# step_dance_wiring.net
KiCad netlist of a schematic drawn in EAGLE
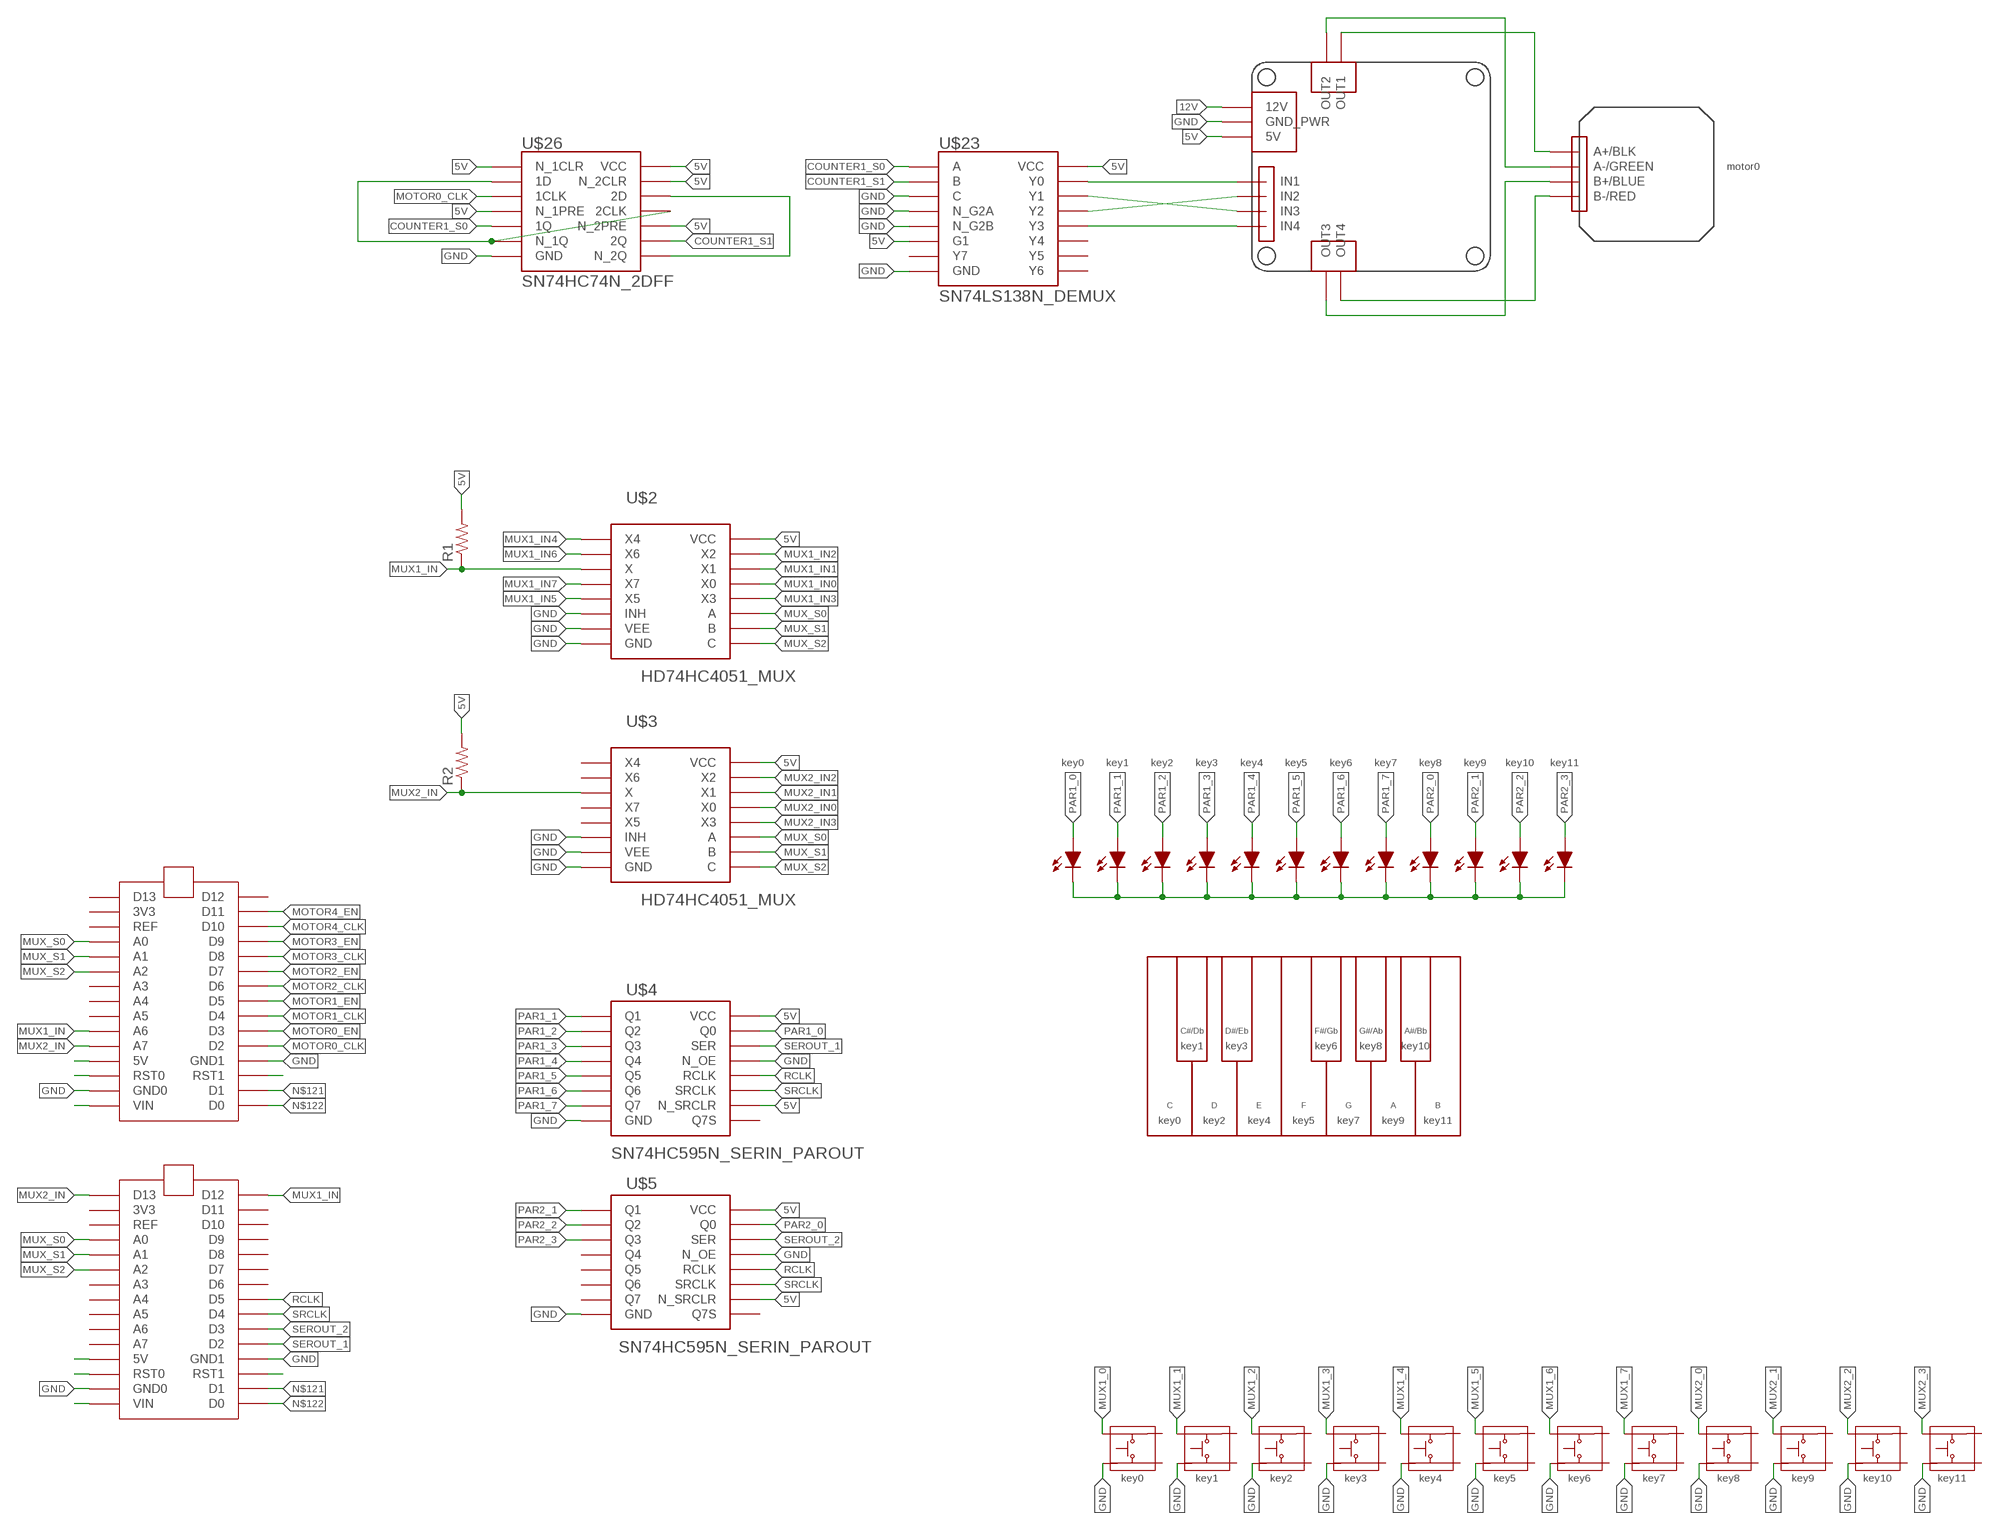
[diagram p0: schematic, sheet 1]

(export (version "E")
  (design (tool "Eeschema 10.0.6"))
  (components
    (comp (ref "LED1")
      (value "LED-5MM")
      (footprint "eagle-import:LED-5MM")
      (libsource (lib "eagle-import") (part "LED-5MM"))
    )
    (comp (ref "LED2")
      (value "LED-5MM")
      (footprint "eagle-import:LED-5MM")
      (libsource (lib "eagle-import") (part "LED-5MM"))
    )
    (comp (ref "LED3")
      (value "LED-5MM")
      (footprint "eagle-import:LED-5MM")
      (libsource (lib "eagle-import") (part "LED-5MM"))
    )
    (comp (ref "LED4")
      (value "LED-5MM")
      (footprint "eagle-import:LED-5MM")
      (libsource (lib "eagle-import") (part "LED-5MM"))
    )
    (comp (ref "LED5")
      (value "LED-5MM")
      (footprint "eagle-import:LED-5MM")
      (libsource (lib "eagle-import") (part "LED-5MM"))
    )
    (comp (ref "LED6")
      (value "LED-5MM")
      (footprint "eagle-import:LED-5MM")
      (libsource (lib "eagle-import") (part "LED-5MM"))
    )
    (comp (ref "LED7")
      (value "LED-5MM")
      (footprint "eagle-import:LED-5MM")
      (libsource (lib "eagle-import") (part "LED-5MM"))
    )
    (comp (ref "LED8")
      (value "LED-5MM")
      (footprint "eagle-import:LED-5MM")
      (libsource (lib "eagle-import") (part "LED-5MM"))
    )
    (comp (ref "LED9")
      (value "LED-5MM")
      (footprint "eagle-import:LED-5MM")
      (libsource (lib "eagle-import") (part "LED-5MM"))
    )
    (comp (ref "LED10")
      (value "LED-5MM")
      (footprint "eagle-import:LED-5MM")
      (libsource (lib "eagle-import") (part "LED-5MM"))
    )
    (comp (ref "LED11")
      (value "LED-5MM")
      (footprint "eagle-import:LED-5MM")
      (libsource (lib "eagle-import") (part "LED-5MM"))
    )
    (comp (ref "LED12")
      (value "LED-5MM")
      (footprint "eagle-import:LED-5MM")
      (libsource (lib "eagle-import") (part "LED-5MM"))
    )
    (comp (ref "R1")
      (value "RES_AXIAL1/2W-0.5")
      (footprint "eagle-import:1_2W-0.5")
      (libsource (lib "eagle-import") (part "RES_AXIAL1/2W-0.5"))
    )
    (comp (ref "R2")
      (value "RES_AXIAL1/2W-0.5")
      (footprint "eagle-import:1_2W-0.5")
      (libsource (lib "eagle-import") (part "RES_AXIAL1/2W-0.5"))
    )
    (comp (ref "U$1")
      (value "ARDUNIO_NANO")
      (footprint "eagle-import:PINS")
      (libsource (lib "eagle-import") (part "ARDUNIO_NANO"))
    )
    (comp (ref "U$2")
      (value "HD74HC4051_MUX")
      (footprint "eagle-import:PINS")
      (libsource (lib "eagle-import") (part "HD74HC4051_MUX"))
    )
    (comp (ref "U$3")
      (value "HD74HC4051_MUX")
      (footprint "eagle-import:PINS")
      (libsource (lib "eagle-import") (part "HD74HC4051_MUX"))
    )
    (comp (ref "U$4")
      (value "SN74HC595N_SERIN_PAROUT")
      (footprint "eagle-import:PINS")
      (libsource (lib "eagle-import") (part "SN74HC595N_SERIN_PAROUT"))
    )
    (comp (ref "U$5")
      (value "SN74HC595N_SERIN_PAROUT")
      (footprint "eagle-import:PINS")
      (libsource (lib "eagle-import") (part "SN74HC595N_SERIN_PAROUT"))
    )
    (comp (ref "U$7")
      (value "MOTOR_DRIVER_HILETGO")
      (footprint "eagle-import:PINS")
      (libsource (lib "eagle-import") (part "MOTOR_DRIVER_HILETGO"))
    )
    (comp (ref "U$8")
      (value "STEPPER")
      (footprint "eagle-import:PINS")
      (libsource (lib "eagle-import") (part "STEPPER"))
    )
    (comp (ref "U$9")
      (value "KEYBOARD")
      (footprint "eagle-import:PINS")
      (libsource (lib "eagle-import") (part "KEYBOARD"))
    )
    (comp (ref "U$10")
      (value "PUSHBUTTON")
      (footprint "eagle-import:PINS")
      (libsource (lib "eagle-import") (part "PUSHBUTTON"))
    )
    (comp (ref "U$11")
      (value "PUSHBUTTON")
      (footprint "eagle-import:PINS")
      (libsource (lib "eagle-import") (part "PUSHBUTTON"))
    )
    (comp (ref "U$12")
      (value "PUSHBUTTON")
      (footprint "eagle-import:PINS")
      (libsource (lib "eagle-import") (part "PUSHBUTTON"))
    )
    (comp (ref "U$13")
      (value "PUSHBUTTON")
      (footprint "eagle-import:PINS")
      (libsource (lib "eagle-import") (part "PUSHBUTTON"))
    )
    (comp (ref "U$14")
      (value "PUSHBUTTON")
      (footprint "eagle-import:PINS")
      (libsource (lib "eagle-import") (part "PUSHBUTTON"))
    )
    (comp (ref "U$15")
      (value "PUSHBUTTON")
      (footprint "eagle-import:PINS")
      (libsource (lib "eagle-import") (part "PUSHBUTTON"))
    )
    (comp (ref "U$16")
      (value "PUSHBUTTON")
      (footprint "eagle-import:PINS")
      (libsource (lib "eagle-import") (part "PUSHBUTTON"))
    )
    (comp (ref "U$17")
      (value "PUSHBUTTON")
      (footprint "eagle-import:PINS")
      (libsource (lib "eagle-import") (part "PUSHBUTTON"))
    )
    (comp (ref "U$18")
      (value "PUSHBUTTON")
      (footprint "eagle-import:PINS")
      (libsource (lib "eagle-import") (part "PUSHBUTTON"))
    )
    (comp (ref "U$19")
      (value "PUSHBUTTON")
      (footprint "eagle-import:PINS")
      (libsource (lib "eagle-import") (part "PUSHBUTTON"))
    )
    (comp (ref "U$20")
      (value "PUSHBUTTON")
      (footprint "eagle-import:PINS")
      (libsource (lib "eagle-import") (part "PUSHBUTTON"))
    )
    (comp (ref "U$21")
      (value "PUSHBUTTON")
      (footprint "eagle-import:PINS")
      (libsource (lib "eagle-import") (part "PUSHBUTTON"))
    )
    (comp (ref "U$22")
      (value "ARDUNIO_NANO")
      (footprint "eagle-import:PINS")
      (libsource (lib "eagle-import") (part "ARDUNIO_NANO"))
    )
    (comp (ref "U$23")
      (value "SN74LS138N_DEMUX")
      (footprint "eagle-import:PINS")
      (libsource (lib "eagle-import") (part "SN74LS138N_DEMUX"))
    )
    (comp (ref "U$26")
      (value "SN74HC74N_2DFF")
      (footprint "eagle-import:PINS")
      (libsource (lib "eagle-import") (part "SN74HC74N_2DFF"))
    )
  )
  (nets
    (net (code "1") (name "5V") (class "Default")
      (node (ref "R1") (pin "2") (pinfunction "2_2") (pintype "passive"))
      (node (ref "R2") (pin "2") (pinfunction "2_2") (pintype "passive"))
      (node (ref "U$2") (pin "P$6") (pinfunction "VCC_P$6") (pintype "output"))
      (node (ref "U$23") (pin "P$4") (pinfunction "G1_P$4") (pintype "output"))
      (node (ref "U$23") (pin "P$8") (pinfunction "VCC_P$8") (pintype "output"))
      (node (ref "U$26") (pin "P$11") (pinfunction "N_2CLR_P$11") (pintype "output"))
      (node (ref "U$26") (pin "P$12") (pinfunction "N_2PRE_P$12") (pintype "output"))
      (node (ref "U$26") (pin "P$14") (pinfunction "VCC_P$14") (pintype "output"))
      (node (ref "U$26") (pin "P$8") (pinfunction "N_1CLR_P$8") (pintype "output"))
      (node (ref "U$26") (pin "P$9") (pinfunction "N_1PRE_P$9") (pintype "output"))
      (node (ref "U$3") (pin "P$6") (pinfunction "VCC_P$6") (pintype "output"))
      (node (ref "U$4") (pin "P$16") (pinfunction "VCC_P$16") (pintype "output"))
      (node (ref "U$4") (pin "P$3") (pinfunction "N_SRCLR_P$3") (pintype "output"))
      (node (ref "U$5") (pin "P$16") (pinfunction "VCC_P$16") (pintype "output"))
      (node (ref "U$5") (pin "P$3") (pinfunction "N_SRCLR_P$3") (pintype "output"))
      (node (ref "U$7") (pin "P$1") (pinfunction "5V_P$1") (pintype "bidirectional"))
    )
    (net (code "2") (name "12V") (class "Default")
      (node (ref "U$7") (pin "P$2") (pinfunction "12V_P$2") (pintype "bidirectional"))
    )
    (net (code "3") (name "COUNTER1_S0") (class "Default")
      (node (ref "U$23") (pin "P$1") (pinfunction "A_P$1") (pintype "output"))
      (node (ref "U$26") (pin "P$3") (pinfunction "1Q_P$3") (pintype "output"))
    )
    (net (code "4") (name "COUNTER1_S1") (class "Default")
      (node (ref "U$23") (pin "P$2") (pinfunction "B_P$2") (pintype "output"))
      (node (ref "U$26") (pin "P$6") (pinfunction "2Q_P$6") (pintype "output"))
    )
    (net (code "5") (name "GND") (class "Default")
      (node (ref "U$1") (pin "P$25") (pinfunction "GND0_P$25") (pintype "bidirectional"))
      (node (ref "U$1") (pin "P$26") (pinfunction "GND1_P$26") (pintype "bidirectional"))
      (node (ref "U$10") (pin "P$2") (pinfunction "P$2_P$2") (pintype "bidirectional"))
      (node (ref "U$11") (pin "P$2") (pinfunction "P$2_P$2") (pintype "bidirectional"))
      (node (ref "U$12") (pin "P$2") (pinfunction "P$2_P$2") (pintype "bidirectional"))
      (node (ref "U$13") (pin "P$2") (pinfunction "P$2_P$2") (pintype "bidirectional"))
      (node (ref "U$14") (pin "P$2") (pinfunction "P$2_P$2") (pintype "bidirectional"))
      (node (ref "U$15") (pin "P$2") (pinfunction "P$2_P$2") (pintype "bidirectional"))
      (node (ref "U$16") (pin "P$2") (pinfunction "P$2_P$2") (pintype "bidirectional"))
      (node (ref "U$17") (pin "P$2") (pinfunction "P$2_P$2") (pintype "bidirectional"))
      (node (ref "U$18") (pin "P$2") (pinfunction "P$2_P$2") (pintype "bidirectional"))
      (node (ref "U$19") (pin "P$2") (pinfunction "P$2_P$2") (pintype "bidirectional"))
      (node (ref "U$2") (pin "P$4") (pinfunction "GND_P$4") (pintype "output"))
      (node (ref "U$2") (pin "P$5") (pinfunction "INH_P$5") (pintype "output"))
      (node (ref "U$2") (pin "P$7") (pinfunction "VEE_P$7") (pintype "output"))
      (node (ref "U$20") (pin "P$2") (pinfunction "P$2_P$2") (pintype "bidirectional"))
      (node (ref "U$21") (pin "P$2") (pinfunction "P$2_P$2") (pintype "bidirectional"))
      (node (ref "U$22") (pin "P$25") (pinfunction "GND0_P$25") (pintype "bidirectional"))
      (node (ref "U$22") (pin "P$26") (pinfunction "GND1_P$26") (pintype "bidirectional"))
      (node (ref "U$23") (pin "P$3") (pinfunction "C_P$3") (pintype "output"))
      (node (ref "U$23") (pin "P$5") (pinfunction "GND_P$5") (pintype "output"))
      (node (ref "U$23") (pin "P$6") (pinfunction "N_G2A_P$6") (pintype "output"))
      (node (ref "U$23") (pin "P$7") (pinfunction "N_G2B_P$7") (pintype "output"))
      (node (ref "U$26") (pin "P$7") (pinfunction "GND_P$7") (pintype "output"))
      (node (ref "U$3") (pin "P$4") (pinfunction "GND_P$4") (pintype "output"))
      (node (ref "U$3") (pin "P$5") (pinfunction "INH_P$5") (pintype "output"))
      (node (ref "U$3") (pin "P$7") (pinfunction "VEE_P$7") (pintype "output"))
      (node (ref "U$4") (pin "P$2") (pinfunction "GND_P$2") (pintype "output"))
      (node (ref "U$4") (pin "P$4") (pinfunction "N_OE_P$4") (pintype "output"))
      (node (ref "U$5") (pin "P$2") (pinfunction "GND_P$2") (pintype "output"))
      (node (ref "U$5") (pin "P$4") (pinfunction "N_OE_P$4") (pintype "output"))
      (node (ref "U$7") (pin "P$3") (pinfunction "GND_PWR_P$3") (pintype "bidirectional"))
    )
    (net (code "6") (name "MOTOR0_CLK") (class "Default")
      (node (ref "U$1") (pin "P$13") (pinfunction "D2_P$13") (pintype "bidirectional"))
      (node (ref "U$26") (pin "P$1") (pinfunction "1CLK_P$1") (pintype "output"))
    )
    (net (code "7") (name "MOTOR0_EN") (class "Default")
      (node (ref "U$1") (pin "P$14") (pinfunction "D3_P$14") (pintype "bidirectional"))
    )
    (net (code "8") (name "MOTOR1_CLK") (class "Default")
      (node (ref "U$1") (pin "P$15") (pinfunction "D4_P$15") (pintype "bidirectional"))
    )
    (net (code "9") (name "MOTOR1_EN") (class "Default")
      (node (ref "U$1") (pin "P$16") (pinfunction "D5_P$16") (pintype "bidirectional"))
    )
    (net (code "10") (name "MOTOR2_CLK") (class "Default")
      (node (ref "U$1") (pin "P$17") (pinfunction "D6_P$17") (pintype "bidirectional"))
    )
    (net (code "11") (name "MOTOR2_EN") (class "Default")
      (node (ref "U$1") (pin "P$18") (pinfunction "D7_P$18") (pintype "bidirectional"))
    )
    (net (code "12") (name "MOTOR3_CLK") (class "Default")
      (node (ref "U$1") (pin "P$19") (pinfunction "D8_P$19") (pintype "bidirectional"))
    )
    (net (code "13") (name "MOTOR3_EN") (class "Default")
      (node (ref "U$1") (pin "P$20") (pinfunction "D9_P$20") (pintype "bidirectional"))
    )
    (net (code "14") (name "MOTOR4_CLK") (class "Default")
      (node (ref "U$1") (pin "P$21") (pinfunction "D10_P$21") (pintype "bidirectional"))
    )
    (net (code "15") (name "MOTOR4_EN") (class "Default")
      (node (ref "U$1") (pin "P$22") (pinfunction "D11_P$22") (pintype "bidirectional"))
    )
    (net (code "16") (name "MUX1_0") (class "Default")
      (node (ref "U$10") (pin "P$1") (pinfunction "P$1_P$1") (pintype "bidirectional"))
    )
    (net (code "17") (name "MUX1_1") (class "Default")
      (node (ref "U$11") (pin "P$1") (pinfunction "P$1_P$1") (pintype "bidirectional"))
    )
    (net (code "18") (name "MUX1_2") (class "Default")
      (node (ref "U$12") (pin "P$1") (pinfunction "P$1_P$1") (pintype "bidirectional"))
    )
    (net (code "19") (name "MUX1_3") (class "Default")
      (node (ref "U$13") (pin "P$1") (pinfunction "P$1_P$1") (pintype "bidirectional"))
    )
    (net (code "20") (name "MUX1_4") (class "Default")
      (node (ref "U$14") (pin "P$1") (pinfunction "P$1_P$1") (pintype "bidirectional"))
    )
    (net (code "21") (name "MUX1_5") (class "Default")
      (node (ref "U$15") (pin "P$1") (pinfunction "P$1_P$1") (pintype "bidirectional"))
    )
    (net (code "22") (name "MUX1_6") (class "Default")
      (node (ref "U$19") (pin "P$1") (pinfunction "P$1_P$1") (pintype "bidirectional"))
    )
    (net (code "23") (name "MUX1_7") (class "Default")
      (node (ref "U$20") (pin "P$1") (pinfunction "P$1_P$1") (pintype "bidirectional"))
    )
    (net (code "24") (name "MUX1_IN") (class "Default")
      (node (ref "R1") (pin "1") (pinfunction "1_1") (pintype "passive"))
      (node (ref "U$1") (pin "P$9") (pinfunction "A6_P$9") (pintype "bidirectional"))
      (node (ref "U$2") (pin "P$8") (pinfunction "X_P$8") (pintype "output"))
      (node (ref "U$22") (pin "P$23") (pinfunction "D12_P$23") (pintype "bidirectional"))
    )
    (net (code "25") (name "MUX1_IN0") (class "Default")
      (node (ref "U$2") (pin "P$9") (pinfunction "X0_P$9") (pintype "output"))
    )
    (net (code "26") (name "MUX1_IN1") (class "Default")
      (node (ref "U$2") (pin "P$10") (pinfunction "X1_P$10") (pintype "output"))
    )
    (net (code "27") (name "MUX1_IN2") (class "Default")
      (node (ref "U$2") (pin "P$11") (pinfunction "X2_P$11") (pintype "output"))
    )
    (net (code "28") (name "MUX1_IN3") (class "Default")
      (node (ref "U$2") (pin "P$12") (pinfunction "X3_P$12") (pintype "output"))
    )
    (net (code "29") (name "MUX1_IN4") (class "Default")
      (node (ref "U$2") (pin "P$13") (pinfunction "X4_P$13") (pintype "output"))
    )
    (net (code "30") (name "MUX1_IN5") (class "Default")
      (node (ref "U$2") (pin "P$14") (pinfunction "X5_P$14") (pintype "output"))
    )
    (net (code "31") (name "MUX1_IN6") (class "Default")
      (node (ref "U$2") (pin "P$15") (pinfunction "X6_P$15") (pintype "output"))
    )
    (net (code "32") (name "MUX1_IN7") (class "Default")
      (node (ref "U$2") (pin "P$16") (pinfunction "X7_P$16") (pintype "output"))
    )
    (net (code "33") (name "MUX2_0") (class "Default")
      (node (ref "U$21") (pin "P$1") (pinfunction "P$1_P$1") (pintype "bidirectional"))
    )
    (net (code "34") (name "MUX2_1") (class "Default")
      (node (ref "U$16") (pin "P$1") (pinfunction "P$1_P$1") (pintype "bidirectional"))
    )
    (net (code "35") (name "MUX2_2") (class "Default")
      (node (ref "U$17") (pin "P$1") (pinfunction "P$1_P$1") (pintype "bidirectional"))
    )
    (net (code "36") (name "MUX2_3") (class "Default")
      (node (ref "U$18") (pin "P$1") (pinfunction "P$1_P$1") (pintype "bidirectional"))
    )
    (net (code "37") (name "MUX2_IN") (class "Default")
      (node (ref "R2") (pin "1") (pinfunction "1_1") (pintype "passive"))
      (node (ref "U$1") (pin "P$10") (pinfunction "A7_P$10") (pintype "bidirectional"))
      (node (ref "U$22") (pin "P$24") (pinfunction "D13_P$24") (pintype "bidirectional"))
      (node (ref "U$3") (pin "P$8") (pinfunction "X_P$8") (pintype "output"))
    )
    (net (code "38") (name "MUX2_IN0") (class "Default")
      (node (ref "U$3") (pin "P$9") (pinfunction "X0_P$9") (pintype "output"))
    )
    (net (code "39") (name "MUX2_IN1") (class "Default")
      (node (ref "U$3") (pin "P$10") (pinfunction "X1_P$10") (pintype "output"))
    )
    (net (code "40") (name "MUX2_IN2") (class "Default")
      (node (ref "U$3") (pin "P$11") (pinfunction "X2_P$11") (pintype "output"))
    )
    (net (code "41") (name "MUX2_IN3") (class "Default")
      (node (ref "U$3") (pin "P$12") (pinfunction "X3_P$12") (pintype "output"))
    )
    (net (code "42") (name "MUX_S0") (class "Default")
      (node (ref "U$1") (pin "P$3") (pinfunction "A0_P$3") (pintype "bidirectional"))
      (node (ref "U$2") (pin "P$1") (pinfunction "A_P$1") (pintype "output"))
      (node (ref "U$22") (pin "P$3") (pinfunction "A0_P$3") (pintype "bidirectional"))
      (node (ref "U$3") (pin "P$1") (pinfunction "A_P$1") (pintype "output"))
    )
    (net (code "43") (name "MUX_S1") (class "Default")
      (node (ref "U$1") (pin "P$4") (pinfunction "A1_P$4") (pintype "bidirectional"))
      (node (ref "U$2") (pin "P$2") (pinfunction "B_P$2") (pintype "output"))
      (node (ref "U$22") (pin "P$4") (pinfunction "A1_P$4") (pintype "bidirectional"))
      (node (ref "U$3") (pin "P$2") (pinfunction "B_P$2") (pintype "output"))
    )
    (net (code "44") (name "MUX_S2") (class "Default")
      (node (ref "U$1") (pin "P$5") (pinfunction "A2_P$5") (pintype "bidirectional"))
      (node (ref "U$2") (pin "P$3") (pinfunction "C_P$3") (pintype "output"))
      (node (ref "U$22") (pin "P$5") (pinfunction "A2_P$5") (pintype "bidirectional"))
      (node (ref "U$3") (pin "P$3") (pinfunction "C_P$3") (pintype "output"))
    )
    (net (code "45") (name "N$121") (class "Default")
      (node (ref "U$1") (pin "P$12") (pinfunction "D1_P$12") (pintype "bidirectional"))
      (node (ref "U$22") (pin "P$12") (pinfunction "D1_P$12") (pintype "bidirectional"))
    )
    (net (code "46") (name "N$122") (class "Default")
      (node (ref "U$1") (pin "P$11") (pinfunction "D0_P$11") (pintype "bidirectional"))
      (node (ref "U$22") (pin "P$11") (pinfunction "D0_P$11") (pintype "bidirectional"))
    )
    (net (code "47") (name "Net-(LED1-C)") (class "Default")
      (node (ref "LED1") (pin "K") (pinfunction "C_K") (pintype "passive"))
      (node (ref "LED10") (pin "K") (pinfunction "C_K") (pintype "passive"))
      (node (ref "LED11") (pin "K") (pinfunction "C_K") (pintype "passive"))
      (node (ref "LED12") (pin "K") (pinfunction "C_K") (pintype "passive"))
      (node (ref "LED2") (pin "K") (pinfunction "C_K") (pintype "passive"))
      (node (ref "LED3") (pin "K") (pinfunction "C_K") (pintype "passive"))
      (node (ref "LED4") (pin "K") (pinfunction "C_K") (pintype "passive"))
      (node (ref "LED5") (pin "K") (pinfunction "C_K") (pintype "passive"))
      (node (ref "LED6") (pin "K") (pinfunction "C_K") (pintype "passive"))
      (node (ref "LED7") (pin "K") (pinfunction "C_K") (pintype "passive"))
      (node (ref "LED8") (pin "K") (pinfunction "C_K") (pintype "passive"))
      (node (ref "LED9") (pin "K") (pinfunction "C_K") (pintype "passive"))
    )
    (net (code "48") (name "Net-(U$7-OUT1)") (class "Default")
      (node (ref "U$7") (pin "P$8") (pinfunction "OUT1_P$8") (pintype "bidirectional"))
      (node (ref "U$8") (pin "P$1") (pinfunction "A+/BLK_P$1") (pintype "bidirectional"))
    )
    (net (code "49") (name "Net-(U$7-OUT2)") (class "Default")
      (node (ref "U$7") (pin "P$9") (pinfunction "OUT2_P$9") (pintype "bidirectional"))
      (node (ref "U$8") (pin "P$2") (pinfunction "A-/GREEN_P$2") (pintype "bidirectional"))
    )
    (net (code "50") (name "Net-(U$7-OUT3)") (class "Default")
      (node (ref "U$7") (pin "P$10") (pinfunction "OUT3_P$10") (pintype "bidirectional"))
      (node (ref "U$8") (pin "P$3") (pinfunction "B+/BLUE_P$3") (pintype "bidirectional"))
    )
    (net (code "51") (name "Net-(U$7-OUT4)") (class "Default")
      (node (ref "U$7") (pin "P$11") (pinfunction "OUT4_P$11") (pintype "bidirectional"))
      (node (ref "U$8") (pin "P$4") (pinfunction "B-/RED_P$4") (pintype "bidirectional"))
    )
    (net (code "52") (name "Net-(U$23-Y0)") (class "Default")
      (node (ref "U$23") (pin "P$9") (pinfunction "Y0_P$9") (pintype "output"))
      (node (ref "U$7") (pin "P$4") (pinfunction "IN1_P$4") (pintype "bidirectional"))
    )
    (net (code "53") (name "Net-(U$23-Y1)") (class "Default")
      (node (ref "U$23") (pin "P$10") (pinfunction "Y1_P$10") (pintype "output"))
      (node (ref "U$7") (pin "P$6") (pinfunction "IN3_P$6") (pintype "bidirectional"))
    )
    (net (code "54") (name "Net-(U$23-Y2)") (class "Default")
      (node (ref "U$23") (pin "P$11") (pinfunction "Y2_P$11") (pintype "output"))
      (node (ref "U$7") (pin "P$5") (pinfunction "IN2_P$5") (pintype "bidirectional"))
    )
    (net (code "55") (name "Net-(U$23-Y3)") (class "Default")
      (node (ref "U$23") (pin "P$12") (pinfunction "Y3_P$12") (pintype "output"))
      (node (ref "U$7") (pin "P$7") (pinfunction "IN4_P$7") (pintype "bidirectional"))
    )
    (net (code "56") (name "Net-(U$26-1D)") (class "Default")
      (node (ref "U$26") (pin "P$10") (pinfunction "N_1Q_P$10") (pintype "output"))
      (node (ref "U$26") (pin "P$2") (pinfunction "1D_P$2") (pintype "output"))
      (node (ref "U$26") (pin "P$4") (pinfunction "2CLK_P$4") (pintype "output"))
    )
    (net (code "57") (name "Net-(U$26-2D)") (class "Default")
      (node (ref "U$26") (pin "P$13") (pinfunction "N_2Q_P$13") (pintype "output"))
      (node (ref "U$26") (pin "P$5") (pinfunction "2D_P$5") (pintype "output"))
    )
    (net (code "58") (name "PAR1_0") (class "Default")
      (node (ref "LED1") (pin "A") (pinfunction "A_A") (pintype "passive"))
      (node (ref "U$4") (pin "P$5") (pinfunction "Q0_P$5") (pintype "output"))
    )
    (net (code "59") (name "PAR1_1") (class "Default")
      (node (ref "LED2") (pin "A") (pinfunction "A_A") (pintype "passive"))
      (node (ref "U$4") (pin "P$6") (pinfunction "Q1_P$6") (pintype "output"))
    )
    (net (code "60") (name "PAR1_2") (class "Default")
      (node (ref "LED3") (pin "A") (pinfunction "A_A") (pintype "passive"))
      (node (ref "U$4") (pin "P$7") (pinfunction "Q2_P$7") (pintype "output"))
    )
    (net (code "61") (name "PAR1_3") (class "Default")
      (node (ref "LED4") (pin "A") (pinfunction "A_A") (pintype "passive"))
      (node (ref "U$4") (pin "P$8") (pinfunction "Q3_P$8") (pintype "output"))
    )
    (net (code "62") (name "PAR1_4") (class "Default")
      (node (ref "LED5") (pin "A") (pinfunction "A_A") (pintype "passive"))
      (node (ref "U$4") (pin "P$9") (pinfunction "Q4_P$9") (pintype "output"))
    )
    (net (code "63") (name "PAR1_5") (class "Default")
      (node (ref "LED6") (pin "A") (pinfunction "A_A") (pintype "passive"))
      (node (ref "U$4") (pin "P$10") (pinfunction "Q5_P$10") (pintype "output"))
    )
    (net (code "64") (name "PAR1_6") (class "Default")
      (node (ref "LED7") (pin "A") (pinfunction "A_A") (pintype "passive"))
      (node (ref "U$4") (pin "P$11") (pinfunction "Q6_P$11") (pintype "output"))
    )
    (net (code "65") (name "PAR1_7") (class "Default")
      (node (ref "LED8") (pin "A") (pinfunction "A_A") (pintype "passive"))
      (node (ref "U$4") (pin "P$12") (pinfunction "Q7_P$12") (pintype "output"))
    )
    (net (code "66") (name "PAR2_0") (class "Default")
      (node (ref "LED9") (pin "A") (pinfunction "A_A") (pintype "passive"))
      (node (ref "U$5") (pin "P$5") (pinfunction "Q0_P$5") (pintype "output"))
    )
    (net (code "67") (name "PAR2_1") (class "Default")
      (node (ref "LED10") (pin "A") (pinfunction "A_A") (pintype "passive"))
      (node (ref "U$5") (pin "P$6") (pinfunction "Q1_P$6") (pintype "output"))
    )
    (net (code "68") (name "PAR2_2") (class "Default")
      (node (ref "LED11") (pin "A") (pinfunction "A_A") (pintype "passive"))
      (node (ref "U$5") (pin "P$7") (pinfunction "Q2_P$7") (pintype "output"))
    )
    (net (code "69") (name "PAR2_3") (class "Default")
      (node (ref "LED12") (pin "A") (pinfunction "A_A") (pintype "passive"))
      (node (ref "U$5") (pin "P$8") (pinfunction "Q3_P$8") (pintype "output"))
    )
    (net (code "70") (name "RCLK") (class "Default")
      (node (ref "U$22") (pin "P$16") (pinfunction "D5_P$16") (pintype "bidirectional"))
      (node (ref "U$4") (pin "P$15") (pinfunction "RCLK_P$15") (pintype "output"))
      (node (ref "U$5") (pin "P$15") (pinfunction "RCLK_P$15") (pintype "output"))
    )
    (net (code "71") (name "SEROUT_1") (class "Default")
      (node (ref "U$22") (pin "P$13") (pinfunction "D2_P$13") (pintype "bidirectional"))
      (node (ref "U$4") (pin "P$1") (pinfunction "SER_P$1") (pintype "output"))
    )
    (net (code "72") (name "SEROUT_2") (class "Default")
      (node (ref "U$22") (pin "P$14") (pinfunction "D3_P$14") (pintype "bidirectional"))
      (node (ref "U$5") (pin "P$1") (pinfunction "SER_P$1") (pintype "output"))
    )
    (net (code "73") (name "SRCLK") (class "Default")
      (node (ref "U$22") (pin "P$15") (pinfunction "D4_P$15") (pintype "bidirectional"))
      (node (ref "U$4") (pin "P$14") (pinfunction "SRCLK_P$14") (pintype "output"))
      (node (ref "U$5") (pin "P$14") (pinfunction "SRCLK_P$14") (pintype "output"))
    )
    (net (code "74") (name "unconnected-(U$1-3V3-PadP$1)") (class "Default")
      (node (ref "U$1") (pin "P$1") (pinfunction "3V3_P$1") (pintype "bidirectional"))
    )
    (net (code "75") (name "unconnected-(U$1-5V-PadP$2)") (class "Default")
      (node (ref "U$1") (pin "P$2") (pinfunction "5V_P$2") (pintype "bidirectional"))
    )
    (net (code "76") (name "unconnected-(U$1-A3-PadP$6)") (class "Default")
      (node (ref "U$1") (pin "P$6") (pinfunction "A3_P$6") (pintype "bidirectional"))
    )
    (net (code "77") (name "unconnected-(U$1-A4-PadP$7)") (class "Default")
      (node (ref "U$1") (pin "P$7") (pinfunction "A4_P$7") (pintype "bidirectional"))
    )
    (net (code "78") (name "unconnected-(U$1-A5-PadP$8)") (class "Default")
      (node (ref "U$1") (pin "P$8") (pinfunction "A5_P$8") (pintype "bidirectional"))
    )
    (net (code "79") (name "unconnected-(U$1-D12-PadP$23)") (class "Default")
      (node (ref "U$1") (pin "P$23") (pinfunction "D12_P$23") (pintype "bidirectional"))
    )
    (net (code "80") (name "unconnected-(U$1-D13-PadP$24)") (class "Default")
      (node (ref "U$1") (pin "P$24") (pinfunction "D13_P$24") (pintype "bidirectional"))
    )
    (net (code "81") (name "unconnected-(U$1-REF-PadP$27)") (class "Default")
      (node (ref "U$1") (pin "P$27") (pinfunction "REF_P$27") (pintype "bidirectional"))
    )
    (net (code "82") (name "unconnected-(U$1-RST0-PadP$28)") (class "Default")
      (node (ref "U$1") (pin "P$28") (pinfunction "RST0_P$28") (pintype "bidirectional"))
    )
    (net (code "83") (name "unconnected-(U$1-RST1-PadP$29)") (class "Default")
      (node (ref "U$1") (pin "P$29") (pinfunction "RST1_P$29") (pintype "bidirectional"))
    )
    (net (code "84") (name "unconnected-(U$1-VIN-PadP$30)") (class "Default")
      (node (ref "U$1") (pin "P$30") (pinfunction "VIN_P$30") (pintype "bidirectional"))
    )
    (net (code "85") (name "unconnected-(U$3-X4-PadP$13)") (class "Default")
      (node (ref "U$3") (pin "P$13") (pinfunction "X4_P$13") (pintype "output"))
    )
    (net (code "86") (name "unconnected-(U$3-X5-PadP$14)") (class "Default")
      (node (ref "U$3") (pin "P$14") (pinfunction "X5_P$14") (pintype "output"))
    )
    (net (code "87") (name "unconnected-(U$3-X6-PadP$15)") (class "Default")
      (node (ref "U$3") (pin "P$15") (pinfunction "X6_P$15") (pintype "output"))
    )
    (net (code "88") (name "unconnected-(U$3-X7-PadP$16)") (class "Default")
      (node (ref "U$3") (pin "P$16") (pinfunction "X7_P$16") (pintype "output"))
    )
    (net (code "89") (name "unconnected-(U$4-Q7S-PadP$13)") (class "Default")
      (node (ref "U$4") (pin "P$13") (pinfunction "Q7S_P$13") (pintype "output"))
    )
    (net (code "90") (name "unconnected-(U$5-Q4-PadP$9)") (class "Default")
      (node (ref "U$5") (pin "P$9") (pinfunction "Q4_P$9") (pintype "output"))
    )
    (net (code "91") (name "unconnected-(U$5-Q5-PadP$10)") (class "Default")
      (node (ref "U$5") (pin "P$10") (pinfunction "Q5_P$10") (pintype "output"))
    )
    (net (code "92") (name "unconnected-(U$5-Q6-PadP$11)") (class "Default")
      (node (ref "U$5") (pin "P$11") (pinfunction "Q6_P$11") (pintype "output"))
    )
    (net (code "93") (name "unconnected-(U$5-Q7-PadP$12)") (class "Default")
      (node (ref "U$5") (pin "P$12") (pinfunction "Q7_P$12") (pintype "output"))
    )
    (net (code "94") (name "unconnected-(U$5-Q7S-PadP$13)") (class "Default")
      (node (ref "U$5") (pin "P$13") (pinfunction "Q7S_P$13") (pintype "output"))
    )
    (net (code "95") (name "unconnected-(U$10-PadP$3)") (class "Default")
      (node (ref "U$10") (pin "P$3") (pinfunction "P$3_P$3") (pintype "bidirectional"))
    )
    (net (code "96") (name "unconnected-(U$10-PadP$4)") (class "Default")
      (node (ref "U$10") (pin "P$4") (pinfunction "P$4_P$4") (pintype "bidirectional"))
    )
    (net (code "97") (name "unconnected-(U$11-PadP$3)") (class "Default")
      (node (ref "U$11") (pin "P$3") (pinfunction "P$3_P$3") (pintype "bidirectional"))
    )
    (net (code "98") (name "unconnected-(U$11-PadP$4)") (class "Default")
      (node (ref "U$11") (pin "P$4") (pinfunction "P$4_P$4") (pintype "bidirectional"))
    )
    (net (code "99") (name "unconnected-(U$12-PadP$3)") (class "Default")
      (node (ref "U$12") (pin "P$3") (pinfunction "P$3_P$3") (pintype "bidirectional"))
    )
    (net (code "100") (name "unconnected-(U$12-PadP$4)") (class "Default")
      (node (ref "U$12") (pin "P$4") (pinfunction "P$4_P$4") (pintype "bidirectional"))
    )
    (net (code "101") (name "unconnected-(U$13-PadP$3)") (class "Default")
      (node (ref "U$13") (pin "P$3") (pinfunction "P$3_P$3") (pintype "bidirectional"))
    )
    (net (code "102") (name "unconnected-(U$13-PadP$4)") (class "Default")
      (node (ref "U$13") (pin "P$4") (pinfunction "P$4_P$4") (pintype "bidirectional"))
    )
    (net (code "103") (name "unconnected-(U$14-PadP$3)") (class "Default")
      (node (ref "U$14") (pin "P$3") (pinfunction "P$3_P$3") (pintype "bidirectional"))
    )
    (net (code "104") (name "unconnected-(U$14-PadP$4)") (class "Default")
      (node (ref "U$14") (pin "P$4") (pinfunction "P$4_P$4") (pintype "bidirectional"))
    )
    (net (code "105") (name "unconnected-(U$15-PadP$3)") (class "Default")
      (node (ref "U$15") (pin "P$3") (pinfunction "P$3_P$3") (pintype "bidirectional"))
    )
    (net (code "106") (name "unconnected-(U$15-PadP$4)") (class "Default")
      (node (ref "U$15") (pin "P$4") (pinfunction "P$4_P$4") (pintype "bidirectional"))
    )
    (net (code "107") (name "unconnected-(U$16-PadP$3)") (class "Default")
      (node (ref "U$16") (pin "P$3") (pinfunction "P$3_P$3") (pintype "bidirectional"))
    )
    (net (code "108") (name "unconnected-(U$16-PadP$4)") (class "Default")
      (node (ref "U$16") (pin "P$4") (pinfunction "P$4_P$4") (pintype "bidirectional"))
    )
    (net (code "109") (name "unconnected-(U$17-PadP$3)") (class "Default")
      (node (ref "U$17") (pin "P$3") (pinfunction "P$3_P$3") (pintype "bidirectional"))
    )
    (net (code "110") (name "unconnected-(U$17-PadP$4)") (class "Default")
      (node (ref "U$17") (pin "P$4") (pinfunction "P$4_P$4") (pintype "bidirectional"))
    )
    (net (code "111") (name "unconnected-(U$18-PadP$3)") (class "Default")
      (node (ref "U$18") (pin "P$3") (pinfunction "P$3_P$3") (pintype "bidirectional"))
    )
    (net (code "112") (name "unconnected-(U$18-PadP$4)") (class "Default")
      (node (ref "U$18") (pin "P$4") (pinfunction "P$4_P$4") (pintype "bidirectional"))
    )
    (net (code "113") (name "unconnected-(U$19-PadP$3)") (class "Default")
      (node (ref "U$19") (pin "P$3") (pinfunction "P$3_P$3") (pintype "bidirectional"))
    )
    (net (code "114") (name "unconnected-(U$19-PadP$4)") (class "Default")
      (node (ref "U$19") (pin "P$4") (pinfunction "P$4_P$4") (pintype "bidirectional"))
    )
    (net (code "115") (name "unconnected-(U$20-PadP$3)") (class "Default")
      (node (ref "U$20") (pin "P$3") (pinfunction "P$3_P$3") (pintype "bidirectional"))
    )
    (net (code "116") (name "unconnected-(U$20-PadP$4)") (class "Default")
      (node (ref "U$20") (pin "P$4") (pinfunction "P$4_P$4") (pintype "bidirectional"))
    )
    (net (code "117") (name "unconnected-(U$21-PadP$3)") (class "Default")
      (node (ref "U$21") (pin "P$3") (pinfunction "P$3_P$3") (pintype "bidirectional"))
    )
    (net (code "118") (name "unconnected-(U$21-PadP$4)") (class "Default")
      (node (ref "U$21") (pin "P$4") (pinfunction "P$4_P$4") (pintype "bidirectional"))
    )
    (net (code "119") (name "unconnected-(U$22-3V3-PadP$1)") (class "Default")
      (node (ref "U$22") (pin "P$1") (pinfunction "3V3_P$1") (pintype "bidirectional"))
    )
    (net (code "120") (name "unconnected-(U$22-5V-PadP$2)") (class "Default")
      (node (ref "U$22") (pin "P$2") (pinfunction "5V_P$2") (pintype "bidirectional"))
    )
    (net (code "121") (name "unconnected-(U$22-A3-PadP$6)") (class "Default")
      (node (ref "U$22") (pin "P$6") (pinfunction "A3_P$6") (pintype "bidirectional"))
    )
    (net (code "122") (name "unconnected-(U$22-A4-PadP$7)") (class "Default")
      (node (ref "U$22") (pin "P$7") (pinfunction "A4_P$7") (pintype "bidirectional"))
    )
    (net (code "123") (name "unconnected-(U$22-A5-PadP$8)") (class "Default")
      (node (ref "U$22") (pin "P$8") (pinfunction "A5_P$8") (pintype "bidirectional"))
    )
    (net (code "124") (name "unconnected-(U$22-A6-PadP$9)") (class "Default")
      (node (ref "U$22") (pin "P$9") (pinfunction "A6_P$9") (pintype "bidirectional"))
    )
    (net (code "125") (name "unconnected-(U$22-A7-PadP$10)") (class "Default")
      (node (ref "U$22") (pin "P$10") (pinfunction "A7_P$10") (pintype "bidirectional"))
    )
    (net (code "126") (name "unconnected-(U$22-D6-PadP$17)") (class "Default")
      (node (ref "U$22") (pin "P$17") (pinfunction "D6_P$17") (pintype "bidirectional"))
    )
    (net (code "127") (name "unconnected-(U$22-D7-PadP$18)") (class "Default")
      (node (ref "U$22") (pin "P$18") (pinfunction "D7_P$18") (pintype "bidirectional"))
    )
    (net (code "128") (name "unconnected-(U$22-D8-PadP$19)") (class "Default")
      (node (ref "U$22") (pin "P$19") (pinfunction "D8_P$19") (pintype "bidirectional"))
    )
    (net (code "129") (name "unconnected-(U$22-D9-PadP$20)") (class "Default")
      (node (ref "U$22") (pin "P$20") (pinfunction "D9_P$20") (pintype "bidirectional"))
    )
    (net (code "130") (name "unconnected-(U$22-D10-PadP$21)") (class "Default")
      (node (ref "U$22") (pin "P$21") (pinfunction "D10_P$21") (pintype "bidirectional"))
    )
    (net (code "131") (name "unconnected-(U$22-D11-PadP$22)") (class "Default")
      (node (ref "U$22") (pin "P$22") (pinfunction "D11_P$22") (pintype "bidirectional"))
    )
    (net (code "132") (name "unconnected-(U$22-REF-PadP$27)") (class "Default")
      (node (ref "U$22") (pin "P$27") (pinfunction "REF_P$27") (pintype "bidirectional"))
    )
    (net (code "133") (name "unconnected-(U$22-RST0-PadP$28)") (class "Default")
      (node (ref "U$22") (pin "P$28") (pinfunction "RST0_P$28") (pintype "bidirectional"))
    )
    (net (code "134") (name "unconnected-(U$22-RST1-PadP$29)") (class "Default")
      (node (ref "U$22") (pin "P$29") (pinfunction "RST1_P$29") (pintype "bidirectional"))
    )
    (net (code "135") (name "unconnected-(U$22-VIN-PadP$30)") (class "Default")
      (node (ref "U$22") (pin "P$30") (pinfunction "VIN_P$30") (pintype "bidirectional"))
    )
    (net (code "136") (name "unconnected-(U$23-Y4-PadP$13)") (class "Default")
      (node (ref "U$23") (pin "P$13") (pinfunction "Y4_P$13") (pintype "output"))
    )
    (net (code "137") (name "unconnected-(U$23-Y5-PadP$14)") (class "Default")
      (node (ref "U$23") (pin "P$14") (pinfunction "Y5_P$14") (pintype "output"))
    )
    (net (code "138") (name "unconnected-(U$23-Y6-PadP$15)") (class "Default")
      (node (ref "U$23") (pin "P$15") (pinfunction "Y6_P$15") (pintype "output"))
    )
    (net (code "139") (name "unconnected-(U$23-Y7-PadP$16)") (class "Default")
      (node (ref "U$23") (pin "P$16") (pinfunction "Y7_P$16") (pintype "output"))
    )
  )
)
